# innovation-board.net
KiCad netlist of a schematic drawn in Altium Designer
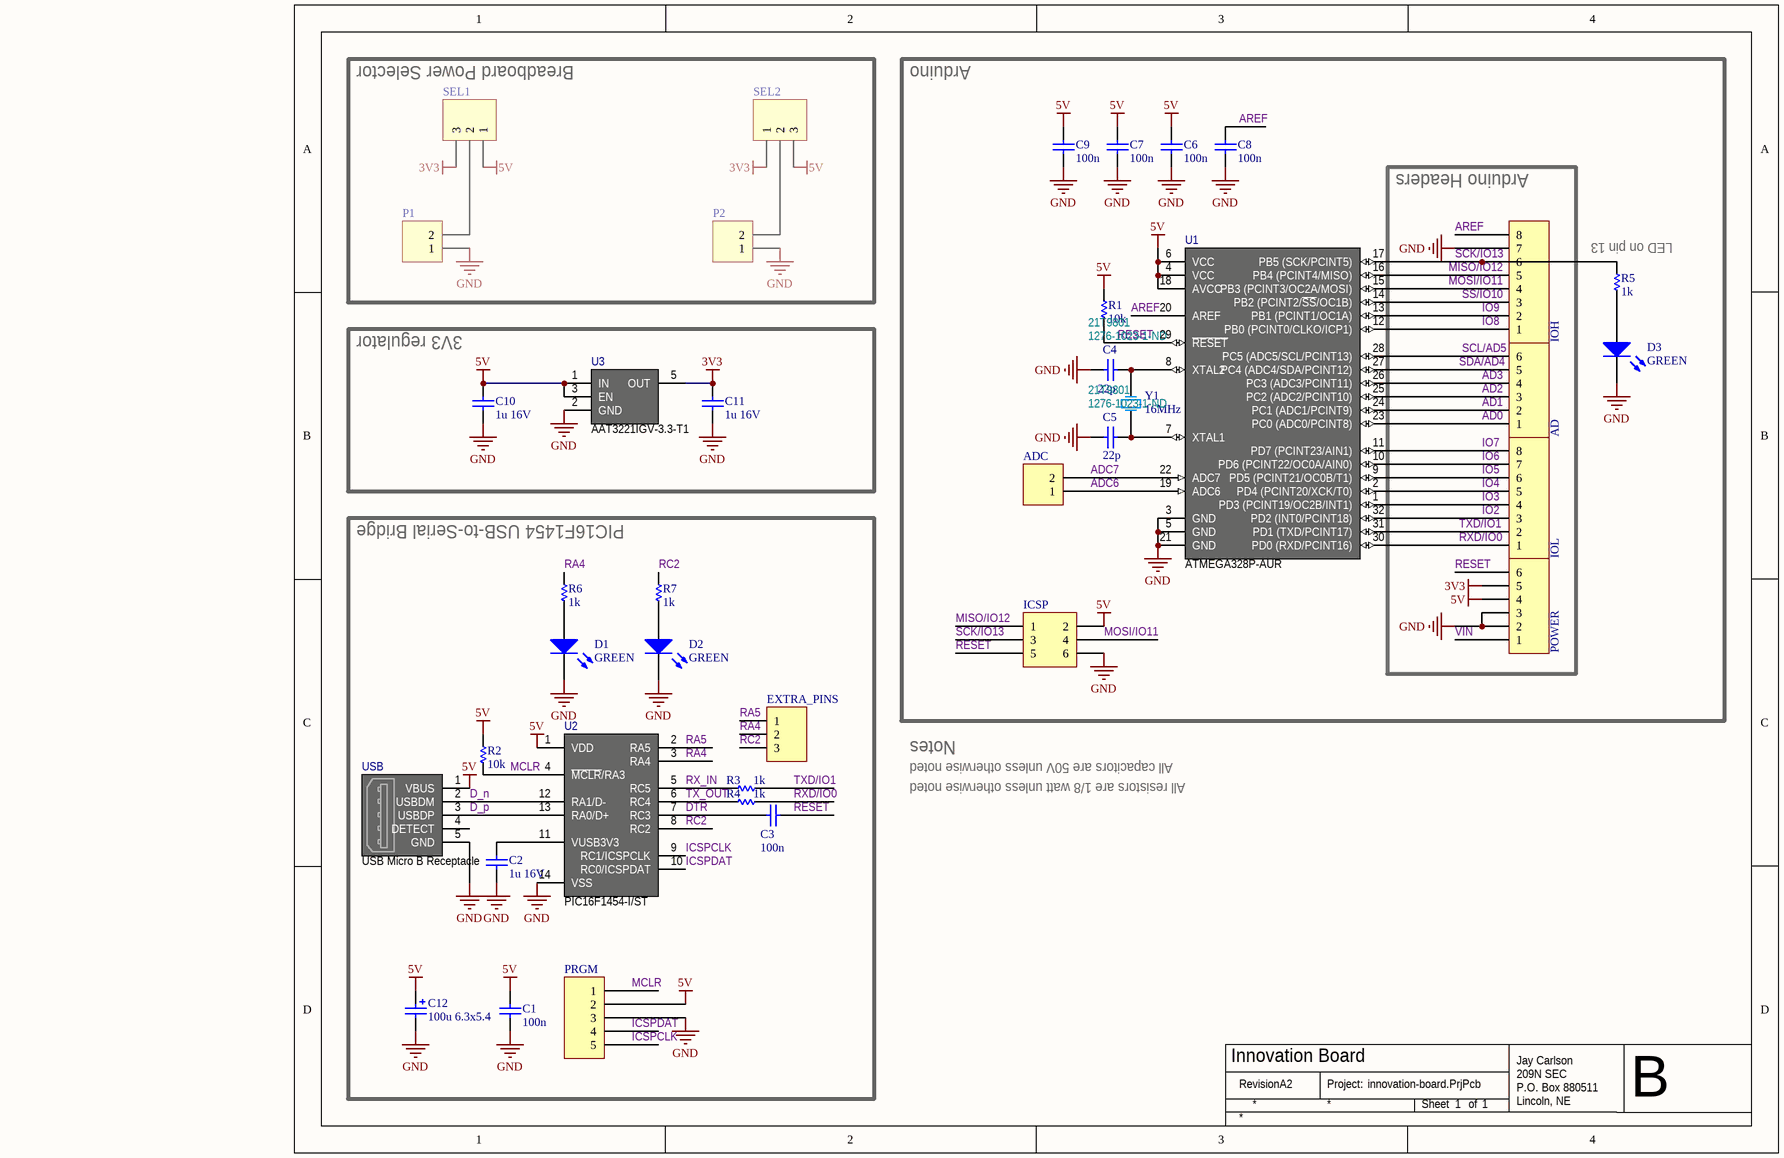
[diagram p0: innovation-board.SchDoc]

(export (version "E")
  (design (tool "Eeschema 10.0.6"))
  (components
    (comp (ref "AD")
      (value "Female Header 6")
      (footprint "HDR1X6")
      (description "Female Header, 6-Pin")
      (fields (field (name "PUBLISHER") "Altium Limited"))
      (libsource (lib "Miscellaneous Connectors") (part "Header 6"))
    )
    (comp (ref "ADC")
      (value "DNI")
      (footprint "HDR1X2")
      (description "Header, 2-Pin")
      (fields (field (name "PUBLISHER") "Altium Limited"))
      (libsource (lib "Miscellaneous Connectors") (part "Header 2"))
    )
    (comp (ref "C1")
      (value "100n")
      (footprint "CAPC1608N")
      (description "100n 0603")
      (fields (field (name "PUBLISHER") "Altium Limited"))
      (libsource (lib "Miscellaneous Devices") (part "Cap Semi"))
    )
    (comp (ref "C2")
      (value "1u 16V")
      (footprint "CAPC1608N")
      (description "1u 16v 0603")
      (fields (field (name "PUBLISHER") "Altium Limited"))
      (libsource (lib "Miscellaneous Devices") (part "Cap Semi"))
    )
    (comp (ref "C3")
      (value "100n")
      (footprint "CAPC1608N")
      (description "Capacitor (Semiconductor SIM Model)")
      (fields (field (name "PUBLISHER") "Altium Limited"))
      (libsource (lib "Miscellaneous Devices") (part "Cap Semi"))
    )
    (comp (ref "C4")
      (value "22p")
      (footprint "CAPC1608N")
      (description "22pf 0603")
      (fields
        (field (name "SUPPLIER PART NUMBER 1") "1276-1023-1-ND")
        (field (name "SUPPLIER PART NUMBER 2") "21T9801")
        (field (name "MANUFACTURER") "TDK")
        (field (name "PUBLISHER") "Altium Limited")
      )
      (libsource (lib "Miscellaneous Devices") (part "Cap Semi"))
    )
    (comp (ref "C5")
      (value "22p")
      (footprint "CAPC1608N")
      (description "22pf 0603")
      (fields
        (field (name "SUPPLIER PART NUMBER 1") "1276-1023-1-ND")
        (field (name "SUPPLIER PART NUMBER 2") "21T9801")
        (field (name "MANUFACTURER") "TDK")
        (field (name "MANUFACTURER PART NUMBER") "MC0603N220J201CT")
        (field (name "PUBLISHER") "Altium Limited")
      )
      (libsource (lib "Miscellaneous Devices") (part "Cap Semi"))
    )
    (comp (ref "C6")
      (value "100n")
      (footprint "CAPC1608N")
      (description "100n 0603")
      (fields (field (name "PUBLISHER") "Altium Limited"))
      (libsource (lib "Miscellaneous Devices") (part "Cap Semi"))
    )
    (comp (ref "C7")
      (value "100n")
      (footprint "CAPC1608N")
      (description "100n 0603")
      (fields (field (name "PUBLISHER") "Altium Limited"))
      (libsource (lib "Miscellaneous Devices") (part "Cap Semi"))
    )
    (comp (ref "C8")
      (value "100n")
      (footprint "CAPC1608N")
      (description "100n 0603")
      (fields (field (name "PUBLISHER") "Altium Limited"))
      (libsource (lib "Miscellaneous Devices") (part "Cap Semi"))
    )
    (comp (ref "C9")
      (value "100n")
      (footprint "CAPC1608N")
      (description "100n 0603")
      (fields (field (name "PUBLISHER") "Altium Limited"))
      (libsource (lib "Miscellaneous Devices") (part "Cap Semi"))
    )
    (comp (ref "C10")
      (value "1u 16V")
      (footprint "CAPC1608N")
      (description "1u 16v 0603")
      (fields (field (name "PUBLISHER") "Altium Limited"))
      (libsource (lib "Miscellaneous Devices") (part "Cap Semi"))
    )
    (comp (ref "C11")
      (value "1u 16V")
      (footprint "CAPC1608N")
      (description "1u 16v 0603")
      (fields (field (name "PUBLISHER") "Altium Limited"))
      (libsource (lib "Miscellaneous Devices") (part "Cap Semi"))
    )
    (comp (ref "C12")
      (value "100u 6.3x5.4")
      (footprint "CAP_63X54")
      (description "Polarized Capacitor (Radial)")
      (fields (field (name "PUBLISHER") "Altium Limited"))
      (libsource (lib "Miscellaneous Devices") (part "Cap Pol1"))
    )
    (comp (ref "D1")
      (value "GREEN")
      (footprint "LTST-C190GKT")
      (description "Green LED 0603")
      (fields (field (name "PUBLISHER") "Altium Limited"))
      (libsource (lib "Miscellaneous Devices") (part "LED_GREEN"))
    )
    (comp (ref "D2")
      (value "GREEN")
      (footprint "LTST-C190GKT")
      (description "Green LED 0603")
      (fields (field (name "PUBLISHER") "Altium Limited"))
      (libsource (lib "Miscellaneous Devices") (part "LED_GREEN"))
    )
    (comp (ref "D3")
      (value "GREEN")
      (footprint "LTST-C190GKT")
      (description "Green LED 0603")
      (fields (field (name "PUBLISHER") "Altium Limited"))
      (libsource (lib "Miscellaneous Devices") (part "LED_GREEN"))
    )
    (comp (ref "EXTRA_PINS")
      (value "DNI")
      (footprint "HDR1X3")
      (description "Header, 3-Pin")
      (fields (field (name "PUBLISHER") "Altium Limited"))
      (libsource (lib "Miscellaneous Connectors") (part "Header 3"))
    )
    (comp (ref "ICSP")
      (value "DNI")
      (footprint "HDR2X3")
      (description "Header, 3-Pin, Dual row")
      (fields (field (name "PUBLISHER") "Altium Limited"))
      (libsource (lib "Miscellaneous Connectors") (part "Header 3X2"))
    )
    (comp (ref "IOH")
      (value "Female Header 8")
      (footprint "HDR1X8")
      (description "Female Header, 8-Pin")
      (fields (field (name "PUBLISHER") "Altium Limited"))
      (libsource (lib "Miscellaneous Connectors") (part "Header 8"))
    )
    (comp (ref "IOL")
      (value "Female Header 8")
      (footprint "HDR1X8")
      (description "Female Header, 8-Pin")
      (fields (field (name "PUBLISHER") "Altium Limited"))
      (libsource (lib "Miscellaneous Connectors") (part "Header 8"))
    )
    (comp (ref "P1")
      (value "DNI")
      (footprint "HDR1X2")
      (description "Header, 2-Pin")
      (fields (field (name "PUBLISHER") "Altium Limited"))
      (libsource (lib "Miscellaneous Connectors") (part "Header 2"))
    )
    (comp (ref "P2")
      (value "DNI")
      (footprint "HDR1X2")
      (description "Header, 2-Pin")
      (fields (field (name "PUBLISHER") "Altium Limited"))
      (libsource (lib "Miscellaneous Connectors") (part "Header 2"))
    )
    (comp (ref "POWER")
      (value "Female Header 6")
      (footprint "HDR1X6")
      (description "Female Header, 6-Pin")
      (fields (field (name "PUBLISHER") "Altium Limited"))
      (libsource (lib "Miscellaneous Connectors") (part "Header 6"))
    )
    (comp (ref "PRGM")
      (value "DNI")
      (footprint "HDR1X5")
      (description "Header, 5-Pin")
      (fields (field (name "PUBLISHER") "Altium Limited"))
      (libsource (lib "Miscellaneous Connectors") (part "Header 5"))
    )
    (comp (ref "R1")
      (value "10k")
      (footprint "RESC1608N")
      (description "10k 0603")
      (fields (field (name "PUBLISHER") "Altium Limited"))
      (libsource (lib "Miscellaneous Devices") (part "Res Semi"))
    )
    (comp (ref "R2")
      (value "10k")
      (footprint "RESC1608N")
      (description "10k 0603")
      (fields (field (name "PUBLISHER") "Altium Limited"))
      (libsource (lib "Miscellaneous Devices") (part "Res Semi"))
    )
    (comp (ref "R3")
      (value "1k")
      (footprint "RESC1608N")
      (description "1k 0603")
      (fields (field (name "PUBLISHER") "Altium Limited"))
      (libsource (lib "Miscellaneous Devices") (part "Res Semi"))
    )
    (comp (ref "R4")
      (value "1k")
      (footprint "RESC1608N")
      (description "1k 0603")
      (fields (field (name "PUBLISHER") "Altium Limited"))
      (libsource (lib "Miscellaneous Devices") (part "Res Semi"))
    )
    (comp (ref "R5")
      (value "1k")
      (footprint "RESC1608N")
      (description "1k 0603")
      (fields (field (name "PUBLISHER") "Altium Limited"))
      (libsource (lib "Miscellaneous Devices") (part "Res Semi"))
    )
    (comp (ref "R6")
      (value "1k")
      (footprint "RESC1608N")
      (description "1k 0603")
      (fields (field (name "PUBLISHER") "Altium Limited"))
      (libsource (lib "Miscellaneous Devices") (part "Res Semi"))
    )
    (comp (ref "R7")
      (value "1k")
      (footprint "RESC1608N")
      (description "1k 0603")
      (fields (field (name "PUBLISHER") "Altium Limited"))
      (libsource (lib "Miscellaneous Devices") (part "Res Semi"))
    )
    (comp (ref "SEL1")
      (value "DNI")
      (footprint "HDR1X3")
      (description "Header, 3-Pin")
      (fields (field (name "PUBLISHER") "Altium Limited"))
      (libsource (lib "Miscellaneous Connectors") (part "Header 3"))
    )
    (comp (ref "SEL2")
      (value "DNI")
      (footprint "HDR1X3")
      (description "Header, 3-Pin")
      (fields (field (name "PUBLISHER") "Altium Limited"))
      (libsource (lib "") (part "Header 3_1"))
    )
    (comp (ref "U1")
      (value "ATMEGA328P-AUR")
      (footprint "QFP80P900X900-32N")
      (description "ATMEL - ATMEGA328P-AUR - MCU, 8BIT, ATMEGA, 20MHZ, TQFP-32")
      (fields (field (name "MANUFACTURER") "ATMEL"))
      (libsource (lib "Atmel MegaAVR") (part "ATMEGA328P-AUR"))
    )
    (comp (ref "U2")
      (value "PIC16F1454-I/ST")
      (footprint "TSOP65P640-14AN")
      (description "8-bit Microcontrollers - MCU 7 KB Flash 512 bytes RAM 48 MHz Int Osc")
      (fields (field (name "MANUFACTURER") "Microchip Technology"))
      (libsource (lib "Microchip Microcontroller 8-Bit") (part "PIC16F1454-I/ST"))
    )
    (comp (ref "U3")
      (value "AAT3221IGV-3.3-T1")
      (footprint "SOT23-5AN")
      (description "3V3 Regulator")
      (libsource (lib "Skyworks LDO Regulator") (part "AAT3221IGV-3.3-T1"))
    )
    (comp (ref "USB")
      (value "USB Micro B Receptacle")
      (footprint "10104110-0001LF")
      (libsource (lib "Miscellaneous Connectors") (part "USB Micro B Receptacle"))
    )
    (comp (ref "Y1")
      (value "16MHz")
      (footprint "HC49/4H_SMX")
      (description "Crystal Oscillator (2 pin)")
      (fields (field (name "PUBLISHER") "Altium Limited"))
      (libsource (lib "Miscellaneous Devices") (part "XTAL"))
    )
  )
  (nets
    (net (code "1") (name "/AD0") (class "Default")
      (node (ref "AD") (pin "1") (pinfunction "1_1") (pintype "passive"))
      (node (ref "U1") (pin "23") (pinfunction "PC0_(ADC0/PCINT8)_23") (pintype "bidirectional"))
    )
    (net (code "2") (name "/AD1") (class "Default")
      (node (ref "AD") (pin "2") (pinfunction "2_2") (pintype "passive"))
      (node (ref "U1") (pin "24") (pinfunction "PC1_(ADC1/PCINT9)_24") (pintype "bidirectional"))
    )
    (net (code "3") (name "/AD2") (class "Default")
      (node (ref "AD") (pin "3") (pinfunction "3_3") (pintype "passive"))
      (node (ref "U1") (pin "25") (pinfunction "PC2_(ADC2/PCINT10)_25") (pintype "bidirectional"))
    )
    (net (code "4") (name "/AD3") (class "Default")
      (node (ref "AD") (pin "4") (pinfunction "4_4") (pintype "passive"))
      (node (ref "U1") (pin "26") (pinfunction "PC3_(ADC3/PCINT11)_26") (pintype "bidirectional"))
    )
    (net (code "5") (name "/ADC6") (class "Default")
      (node (ref "ADC") (pin "1") (pinfunction "1_1") (pintype "passive"))
      (node (ref "U1") (pin "19") (pinfunction "ADC6_19") (pintype "input"))
    )
    (net (code "6") (name "/ADC7") (class "Default")
      (node (ref "ADC") (pin "2") (pinfunction "2_2") (pintype "passive"))
      (node (ref "U1") (pin "22") (pinfunction "ADC7_22") (pintype "input"))
    )
    (net (code "7") (name "/AREF") (class "Default")
      (node (ref "C8") (pin "2") (pinfunction "2_2") (pintype "passive"))
      (node (ref "IOH") (pin "8") (pinfunction "8_8") (pintype "passive"))
      (node (ref "U1") (pin "20") (pinfunction "AREF_20") (pintype "passive"))
    )
    (net (code "8") (name "/DTR") (class "Default")
      (node (ref "C3") (pin "1") (pinfunction "1_1") (pintype "passive"))
      (node (ref "U2") (pin "7") (pinfunction "RC3_7") (pintype "power_in"))
    )
    (net (code "9") (name "/D_n") (class "Default")
      (node (ref "U2") (pin "12") (pinfunction "RA1/D-_12") (pintype "power_in"))
      (node (ref "USB") (pin "2") (pinfunction "USBDM_2") (pintype "power_in"))
    )
    (net (code "10") (name "/D_p") (class "Default")
      (node (ref "U2") (pin "13") (pinfunction "RA0/D+_13") (pintype "power_in"))
      (node (ref "USB") (pin "3") (pinfunction "USBDP_3") (pintype "power_in"))
    )
    (net (code "11") (name "/ICSPCLK") (class "Default")
      (node (ref "PRGM") (pin "5") (pinfunction "5_5") (pintype "passive"))
      (node (ref "U2") (pin "9") (pinfunction "RC1/ICSPCLK_9") (pintype "power_in"))
    )
    (net (code "12") (name "/ICSPDAT") (class "Default")
      (node (ref "PRGM") (pin "4") (pinfunction "4_4") (pintype "passive"))
      (node (ref "U2") (pin "10") (pinfunction "RC0/ICSPDAT_10") (pintype "power_in"))
    )
    (net (code "13") (name "/IO2") (class "Default")
      (node (ref "IOL") (pin "3") (pinfunction "3_3") (pintype "passive"))
      (node (ref "U1") (pin "32") (pinfunction "PD2_(INT0/PCINT18)_32") (pintype "bidirectional"))
    )
    (net (code "14") (name "/IO3") (class "Default")
      (node (ref "IOL") (pin "4") (pinfunction "4_4") (pintype "passive"))
      (node (ref "U1") (pin "1") (pinfunction "PD3_(PCINT19/OC2B/INT1)_1") (pintype "bidirectional"))
    )
    (net (code "15") (name "/IO4") (class "Default")
      (node (ref "IOL") (pin "5") (pinfunction "5_5") (pintype "passive"))
      (node (ref "U1") (pin "2") (pinfunction "PD4_(PCINT20/XCK/T0)_2") (pintype "bidirectional"))
    )
    (net (code "16") (name "/IO5") (class "Default")
      (node (ref "IOL") (pin "6") (pinfunction "6_6") (pintype "passive"))
      (node (ref "U1") (pin "9") (pinfunction "PD5_(PCINT21/OC0B/T1)_9") (pintype "bidirectional"))
    )
    (net (code "17") (name "/IO6") (class "Default")
      (node (ref "IOL") (pin "7") (pinfunction "7_7") (pintype "passive"))
      (node (ref "U1") (pin "10") (pinfunction "PD6_(PCINT22/OC0A/AIN0)_10") (pintype "bidirectional"))
    )
    (net (code "18") (name "/IO7") (class "Default")
      (node (ref "IOL") (pin "8") (pinfunction "8_8") (pintype "passive"))
      (node (ref "U1") (pin "11") (pinfunction "PD7_(PCINT23/AIN1)_11") (pintype "bidirectional"))
    )
    (net (code "19") (name "/IO8") (class "Default")
      (node (ref "IOH") (pin "1") (pinfunction "1_1") (pintype "passive"))
      (node (ref "U1") (pin "12") (pinfunction "PB0_(PCINT0/CLKO/ICP1)_12") (pintype "bidirectional"))
    )
    (net (code "20") (name "/IO9") (class "Default")
      (node (ref "IOH") (pin "2") (pinfunction "2_2") (pintype "passive"))
      (node (ref "U1") (pin "13") (pinfunction "PB1_(PCINT1/OC1A)_13") (pintype "bidirectional"))
    )
    (net (code "21") (name "/MCLR") (class "Default")
      (node (ref "PRGM") (pin "1") (pinfunction "1_1") (pintype "passive"))
      (node (ref "R2") (pin "1") (pinfunction "1_1") (pintype "passive"))
      (node (ref "U2") (pin "4") (pinfunction "~{MCLR}/RA3_4") (pintype "power_in"))
    )
    (net (code "22") (name "/MISO{slash}IO12") (class "Default")
      (node (ref "ICSP") (pin "1") (pinfunction "1_1") (pintype "passive"))
      (node (ref "IOH") (pin "5") (pinfunction "5_5") (pintype "passive"))
      (node (ref "U1") (pin "16") (pinfunction "PB4_(PCINT4/MISO)_16") (pintype "bidirectional"))
    )
    (net (code "23") (name "/MOSI{slash}IO11") (class "Default")
      (node (ref "ICSP") (pin "4") (pinfunction "4_4") (pintype "passive"))
      (node (ref "IOH") (pin "4") (pinfunction "4_4") (pintype "passive"))
      (node (ref "U1") (pin "15") (pinfunction "PB3_(PCINT3/OC2A/MOSI)_15") (pintype "bidirectional"))
    )
    (net (code "24") (name "/RA4") (class "Default")
      (node (ref "EXTRA_PINS") (pin "2") (pinfunction "2_2") (pintype "passive"))
      (node (ref "R6") (pin "2") (pinfunction "2_2") (pintype "passive"))
      (node (ref "U2") (pin "3") (pinfunction "RA4_3") (pintype "power_in"))
    )
    (net (code "25") (name "/RA5") (class "Default")
      (node (ref "EXTRA_PINS") (pin "1") (pinfunction "1_1") (pintype "passive"))
      (node (ref "U2") (pin "2") (pinfunction "RA5_2") (pintype "power_in"))
    )
    (net (code "26") (name "/RC2") (class "Default")
      (node (ref "EXTRA_PINS") (pin "3") (pinfunction "3_3") (pintype "passive"))
      (node (ref "R7") (pin "2") (pinfunction "2_2") (pintype "passive"))
      (node (ref "U2") (pin "8") (pinfunction "RC2_8") (pintype "power_in"))
    )
    (net (code "27") (name "/RESET") (class "Default")
      (node (ref "C3") (pin "2") (pinfunction "2_2") (pintype "passive"))
      (node (ref "ICSP") (pin "5") (pinfunction "5_5") (pintype "passive"))
      (node (ref "POWER") (pin "6") (pinfunction "6_6") (pintype "passive"))
      (node (ref "R1") (pin "2") (pinfunction "2_2") (pintype "passive"))
      (node (ref "U1") (pin "29") (pinfunction "~{RESET}_29") (pintype "bidirectional"))
    )
    (net (code "28") (name "/RXD{slash}IO0") (class "Default")
      (node (ref "IOL") (pin "1") (pinfunction "1_1") (pintype "passive"))
      (node (ref "R4") (pin "2") (pinfunction "2_2") (pintype "passive"))
      (node (ref "U1") (pin "30") (pinfunction "PD0_(RXD/PCINT16)_30") (pintype "bidirectional"))
    )
    (net (code "29") (name "/RX_IN") (class "Default")
      (node (ref "R3") (pin "1") (pinfunction "1_1") (pintype "passive"))
      (node (ref "U2") (pin "5") (pinfunction "RC5_5") (pintype "power_in"))
    )
    (net (code "30") (name "/SCK{slash}IO13") (class "Default")
      (node (ref "ICSP") (pin "3") (pinfunction "3_3") (pintype "passive"))
      (node (ref "IOH") (pin "6") (pinfunction "6_6") (pintype "passive"))
      (node (ref "R5") (pin "2") (pinfunction "2_2") (pintype "passive"))
      (node (ref "U1") (pin "17") (pinfunction "PB5_(SCK/PCINT5)_17") (pintype "bidirectional"))
    )
    (net (code "31") (name "/SCL{slash}AD5") (class "Default")
      (node (ref "AD") (pin "6") (pinfunction "6_6") (pintype "passive"))
      (node (ref "U1") (pin "28") (pinfunction "PC5_(ADC5/SCL/PCINT13)_28") (pintype "bidirectional"))
    )
    (net (code "32") (name "/SDA{slash}AD4") (class "Default")
      (node (ref "AD") (pin "5") (pinfunction "5_5") (pintype "passive"))
      (node (ref "U1") (pin "27") (pinfunction "PC4_(ADC4/SDA/PCINT12)_27") (pintype "bidirectional"))
    )
    (net (code "33") (name "/SS{slash}IO10") (class "Default")
      (node (ref "IOH") (pin "3") (pinfunction "3_3") (pintype "passive"))
      (node (ref "U1") (pin "14") (pinfunction "PB2_(PCINT2/~{SS}/OC1B)_14") (pintype "bidirectional"))
    )
    (net (code "34") (name "/TXD{slash}IO1") (class "Default")
      (node (ref "IOL") (pin "2") (pinfunction "2_2") (pintype "passive"))
      (node (ref "R3") (pin "2") (pinfunction "2_2") (pintype "passive"))
      (node (ref "U1") (pin "31") (pinfunction "PD1_(TXD/PCINT17)_31") (pintype "bidirectional"))
    )
    (net (code "35") (name "/TX_OUT") (class "Default")
      (node (ref "R4") (pin "1") (pinfunction "1_1") (pintype "passive"))
      (node (ref "U2") (pin "6") (pinfunction "RC4_6") (pintype "power_in"))
    )
    (net (code "36") (name "/VIN") (class "Default")
      (node (ref "POWER") (pin "1") (pinfunction "1_1") (pintype "passive"))
    )
    (net (code "37") (name "3V3") (class "Default")
      (node (ref "C11") (pin "1") (pinfunction "1_1") (pintype "passive"))
      (node (ref "POWER") (pin "5") (pinfunction "5_5") (pintype "passive"))
      (node (ref "SEL1") (pin "3") (pinfunction "3_3") (pintype "passive"))
      (node (ref "SEL2") (pin "1") (pinfunction "1_1") (pintype "passive"))
      (node (ref "U3") (pin "5") (pinfunction "OUT_5") (pintype "passive"))
    )
    (net (code "38") (name "5V") (class "Default")
      (node (ref "C1") (pin "2") (pinfunction "2_2") (pintype "passive"))
      (node (ref "C10") (pin "1") (pinfunction "1_1") (pintype "passive"))
      (node (ref "C12") (pin "1") (pinfunction "1_1") (pintype "passive"))
      (node (ref "C6") (pin "2") (pinfunction "2_2") (pintype "passive"))
      (node (ref "C7") (pin "2") (pinfunction "2_2") (pintype "passive"))
      (node (ref "C9") (pin "2") (pinfunction "2_2") (pintype "passive"))
      (node (ref "ICSP") (pin "2") (pinfunction "2_2") (pintype "passive"))
      (node (ref "POWER") (pin "4") (pinfunction "4_4") (pintype "passive"))
      (node (ref "PRGM") (pin "2") (pinfunction "2_2") (pintype "passive"))
      (node (ref "R1") (pin "1") (pinfunction "1_1") (pintype "passive"))
      (node (ref "R2") (pin "2") (pinfunction "2_2") (pintype "passive"))
      (node (ref "SEL1") (pin "1") (pinfunction "1_1") (pintype "passive"))
      (node (ref "SEL2") (pin "3") (pinfunction "3_3") (pintype "passive"))
      (node (ref "U1") (pin "18") (pinfunction "AVCC_18") (pintype "power_in"))
      (node (ref "U1") (pin "4") (pinfunction "VCC_4") (pintype "power_in"))
      (node (ref "U1") (pin "6") (pinfunction "VCC_6") (pintype "power_in"))
      (node (ref "U2") (pin "1") (pinfunction "VDD_1") (pintype "power_in"))
      (node (ref "U3") (pin "1") (pinfunction "IN_1") (pintype "passive"))
      (node (ref "U3") (pin "3") (pinfunction "EN_3") (pintype "passive"))
      (node (ref "USB") (pin "1") (pinfunction "VBUS_1") (pintype "power_in"))
    )
    (net (code "39") (name "GND") (class "Default")
      (node (ref "C1") (pin "1") (pinfunction "1_1") (pintype "passive"))
      (node (ref "C10") (pin "2") (pinfunction "2_2") (pintype "passive"))
      (node (ref "C11") (pin "2") (pinfunction "2_2") (pintype "passive"))
      (node (ref "C12") (pin "2") (pinfunction "2_2") (pintype "passive"))
      (node (ref "C2") (pin "1") (pinfunction "1_1") (pintype "passive"))
      (node (ref "C4") (pin "1") (pinfunction "1_1") (pintype "passive"))
      (node (ref "C5") (pin "1") (pinfunction "1_1") (pintype "passive"))
      (node (ref "C6") (pin "1") (pinfunction "1_1") (pintype "passive"))
      (node (ref "C7") (pin "1") (pinfunction "1_1") (pintype "passive"))
      (node (ref "C8") (pin "1") (pinfunction "1_1") (pintype "passive"))
      (node (ref "C9") (pin "1") (pinfunction "1_1") (pintype "passive"))
      (node (ref "D1") (pin "2") (pinfunction "K_2") (pintype "passive"))
      (node (ref "D2") (pin "2") (pinfunction "K_2") (pintype "passive"))
      (node (ref "D3") (pin "2") (pinfunction "K_2") (pintype "passive"))
      (node (ref "ICSP") (pin "6") (pinfunction "6_6") (pintype "passive"))
      (node (ref "IOH") (pin "7") (pinfunction "7_7") (pintype "passive"))
      (node (ref "P1") (pin "1") (pinfunction "1_1") (pintype "passive"))
      (node (ref "P2") (pin "1") (pinfunction "1_1") (pintype "passive"))
      (node (ref "POWER") (pin "2") (pinfunction "2_2") (pintype "passive"))
      (node (ref "POWER") (pin "3") (pinfunction "3_3") (pintype "passive"))
      (node (ref "PRGM") (pin "3") (pinfunction "3_3") (pintype "passive"))
      (node (ref "U1") (pin "21") (pinfunction "GND_21") (pintype "power_in"))
      (node (ref "U1") (pin "3") (pinfunction "GND_3") (pintype "power_in"))
      (node (ref "U1") (pin "5") (pinfunction "GND_5") (pintype "power_in"))
      (node (ref "U2") (pin "14") (pinfunction "VSS_14") (pintype "power_in"))
      (node (ref "U3") (pin "2") (pinfunction "GND_2") (pintype "passive"))
      (node (ref "USB") (pin "5") (pinfunction "GND_5") (pintype "power_in"))
    )
    (net (code "40") (name "Net-(D1-A)") (class "Default")
      (node (ref "D1") (pin "1") (pinfunction "A_1") (pintype "passive"))
      (node (ref "R6") (pin "1") (pinfunction "1_1") (pintype "passive"))
    )
    (net (code "41") (name "Net-(D2-A)") (class "Default")
      (node (ref "D2") (pin "1") (pinfunction "A_1") (pintype "passive"))
      (node (ref "R7") (pin "1") (pinfunction "1_1") (pintype "passive"))
    )
    (net (code "42") (name "Net-(D3-A)") (class "Default")
      (node (ref "D3") (pin "1") (pinfunction "A_1") (pintype "passive"))
      (node (ref "R5") (pin "1") (pinfunction "1_1") (pintype "passive"))
    )
    (net (code "43") (name "Net-(P1-Pad2)") (class "Default")
      (node (ref "P1") (pin "2") (pinfunction "2_2") (pintype "passive"))
      (node (ref "SEL1") (pin "2") (pinfunction "2_2") (pintype "passive"))
    )
    (net (code "44") (name "Net-(P2-Pad2)") (class "Default")
      (node (ref "P2") (pin "2") (pinfunction "2_2") (pintype "passive"))
      (node (ref "SEL2") (pin "2") (pinfunction "2_2") (pintype "passive"))
    )
    (net (code "45") (name "Net-(U1-XTAL1)") (class "Default")
      (node (ref "C5") (pin "2") (pinfunction "2_2") (pintype "passive"))
      (node (ref "U1") (pin "7") (pinfunction "XTAL1_7") (pintype "bidirectional"))
      (node (ref "Y1") (pin "2") (pinfunction "OSC2_2") (pintype "passive"))
    )
    (net (code "46") (name "Net-(U1-XTAL2)") (class "Default")
      (node (ref "C4") (pin "2") (pinfunction "2_2") (pintype "passive"))
      (node (ref "U1") (pin "8") (pinfunction "XTAL2_8") (pintype "bidirectional"))
      (node (ref "Y1") (pin "1") (pinfunction "OSC1_1") (pintype "passive"))
    )
    (net (code "47") (name "Net-(U2-VUSB3V3)") (class "Default")
      (node (ref "C2") (pin "2") (pinfunction "2_2") (pintype "passive"))
      (node (ref "U2") (pin "11") (pinfunction "VUSB3V3_11") (pintype "power_in"))
    )
    (net (code "48") (name "unconnected-(USB-DETECT-Pad4)") (class "Default")
      (node (ref "USB") (pin "4") (pinfunction "DETECT_4") (pintype "power_in"))
    )
  )
)
